# 4-Channel-Relay-Driver-Module-Circuit_20.net
KiCad netlist of a schematic drawn in Altium Designer
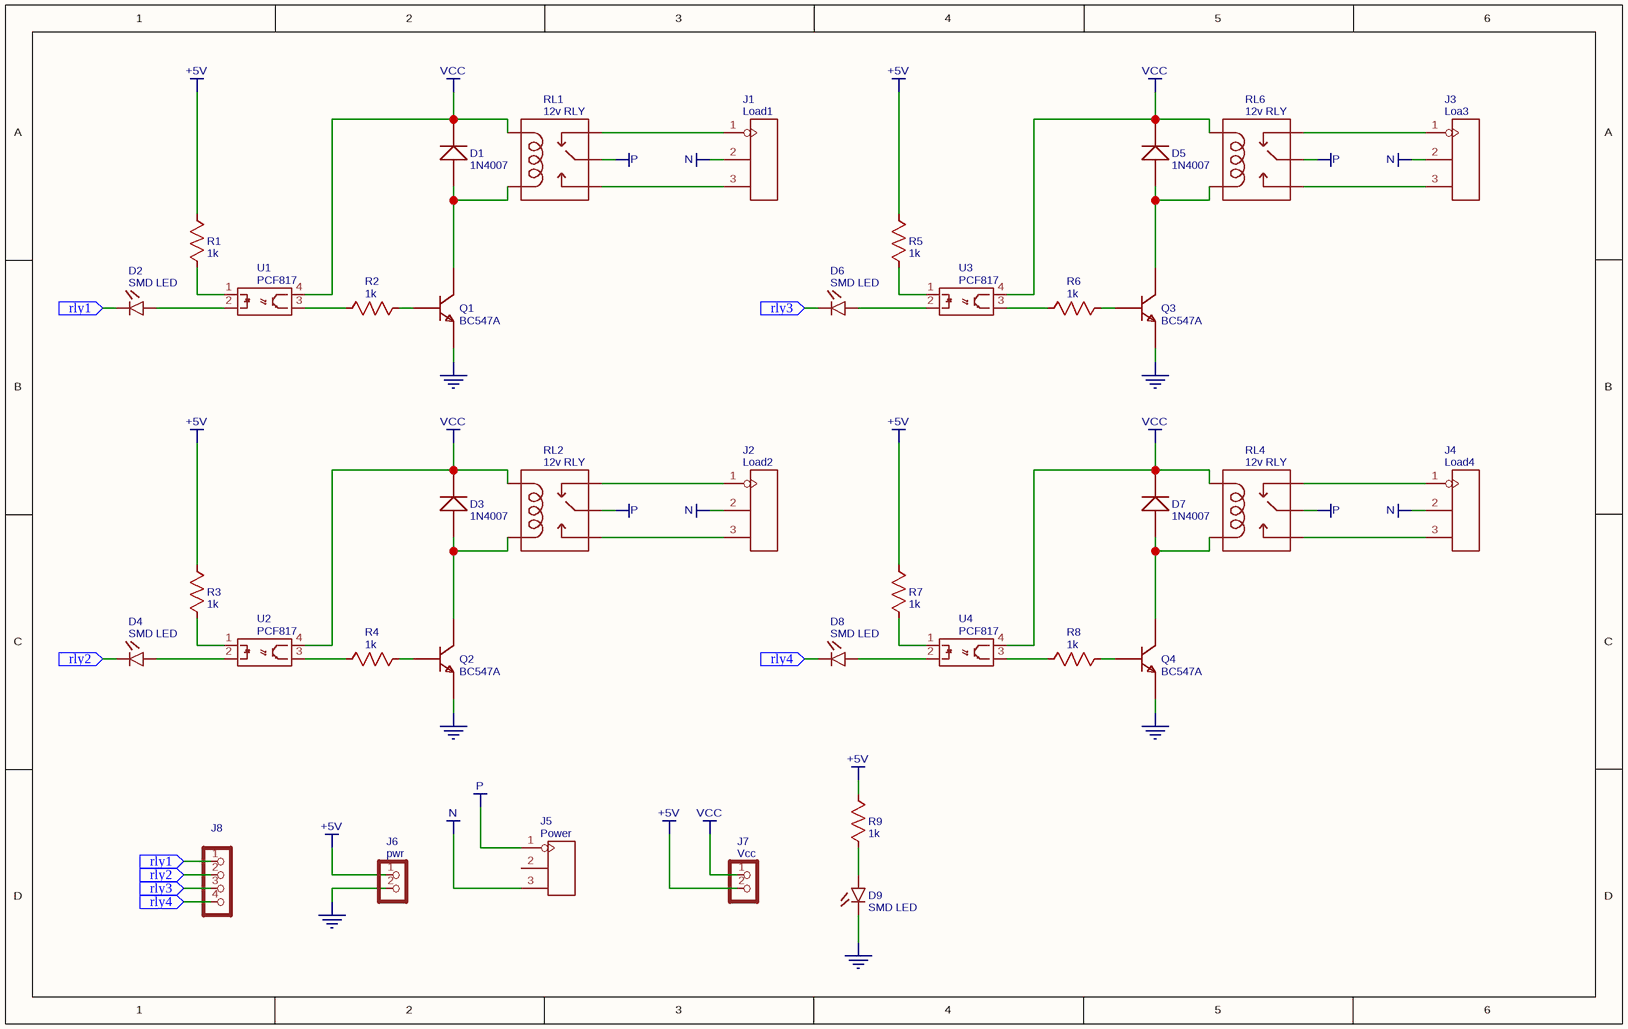
[diagram p0: 4-Channel-Relay-Driver-Module-Circuit_2024-05-24.schdoc]

(export (version "E")
  (design (tool "Eeschema 10.0.6"))
  (components
    (comp (ref "D1")
      (value "1N4007")
      (description "1.0 Ampere General Purpose Rectifier")
      (fields (field (name "MANUFACTURER PART") "?"))
      (libsource (lib "altium-import") (part "root_1_1N4007_"))
    )
    (comp (ref "D2")
      (value "SMD LED")
      (fields (field (name "MANUFACTURER PART") "?"))
      (libsource (lib "altium-import") (part "root_3_SMD LED_"))
    )
    (comp (ref "D3")
      (value "1N4007")
      (description "1.0 Ampere General Purpose Rectifier")
      (fields (field (name "MANUFACTURER PART") "?"))
      (libsource (lib "altium-import") (part "root_1_1N4007_"))
    )
    (comp (ref "D4")
      (value "SMD LED")
      (fields (field (name "MANUFACTURER PART") "?"))
      (libsource (lib "altium-import") (part "root_3_SMD LED_"))
    )
    (comp (ref "D5")
      (value "1N4007")
      (description "1.0 Ampere General Purpose Rectifier")
      (fields (field (name "MANUFACTURER PART") "?"))
      (libsource (lib "altium-import") (part "root_1_1N4007_"))
    )
    (comp (ref "D6")
      (value "SMD LED")
      (fields (field (name "MANUFACTURER PART") "?"))
      (libsource (lib "altium-import") (part "root_3_SMD LED_"))
    )
    (comp (ref "D7")
      (value "1N4007")
      (description "1.0 Ampere General Purpose Rectifier")
      (fields (field (name "MANUFACTURER PART") "?"))
      (libsource (lib "altium-import") (part "root_1_1N4007_"))
    )
    (comp (ref "D8")
      (value "SMD LED")
      (fields (field (name "MANUFACTURER PART") "?"))
      (libsource (lib "altium-import") (part "root_3_SMD LED_"))
    )
    (comp (ref "D9")
      (value "SMD LED")
      (fields (field (name "MANUFACTURER PART") "?"))
      (libsource (lib "altium-import") (part "root_0_SMD LED_"))
    )
    (comp (ref "J1")
      (value "Load1")
      (description "Screw Terminal")
      (fields (field (name "MANUFACTURER PART") "?"))
      (libsource (lib "altium-import") (part "root_0_Load1_"))
    )
    (comp (ref "J2")
      (value "Load2")
      (description "Screw Terminal")
      (fields (field (name "MANUFACTURER PART") "?"))
      (libsource (lib "altium-import") (part "root_0_Load2_"))
    )
    (comp (ref "J3")
      (value "Loa3")
      (description "Screw Terminal")
      (fields (field (name "MANUFACTURER PART") "?"))
      (libsource (lib "altium-import") (part "root_0_Loa3_"))
    )
    (comp (ref "J4")
      (value "Load4")
      (description "Screw Terminal")
      (fields (field (name "MANUFACTURER PART") "?"))
      (libsource (lib "altium-import") (part "root_0_Load4_"))
    )
    (comp (ref "J5")
      (value "Power")
      (description "Screw Terminal")
      (fields (field (name "MANUFACTURER PART") "?"))
      (libsource (lib "altium-import") (part "root_0_Power_"))
    )
    (comp (ref "J6")
      (value "pwr")
      (fields (field (name "MANUFACTURER PART") "?") (field (name "CONTRIBUTOR") "DangerousPrototype"))
      (libsource (lib "altium-import") (part "root_0_pwr_"))
    )
    (comp (ref "J7")
      (value "Vcc")
      (fields (field (name "MANUFACTURER PART") "?") (field (name "CONTRIBUTOR") "DangerousPrototype"))
      (libsource (lib "altium-import") (part "root_0_Vcc_"))
    )
    (comp (ref "J8")
      (value "+5v")
      (fields (field (name "MANUFACTURER PART") "?") (field (name "CONTRIBUTOR") "DangerousPrototype"))
      (libsource (lib "altium-import") (part "root_0_+5v_"))
    )
    (comp (ref "Q1")
      (value "BC547A")
      (description "Amplifier Transistor NPN Silicon")
      (fields (field (name "MANUFACTURER PART") "?"))
      (libsource (lib "altium-import") (part "root_0_BC547A_"))
    )
    (comp (ref "Q2")
      (value "BC547A")
      (description "Amplifier Transistor NPN Silicon")
      (fields (field (name "MANUFACTURER PART") "?"))
      (libsource (lib "altium-import") (part "root_0_BC547A_"))
    )
    (comp (ref "Q3")
      (value "BC547A")
      (description "Amplifier Transistor NPN Silicon")
      (fields (field (name "MANUFACTURER PART") "?"))
      (libsource (lib "altium-import") (part "root_0_BC547A_"))
    )
    (comp (ref "Q4")
      (value "BC547A")
      (description "Amplifier Transistor NPN Silicon")
      (fields (field (name "MANUFACTURER PART") "?"))
      (libsource (lib "altium-import") (part "root_0_BC547A_"))
    )
    (comp (ref "R1")
      (value "1k")
      (fields (field (name "MANUFACTURER PART") "?"))
      (libsource (lib "altium-import") (part "root_1_1k_"))
    )
    (comp (ref "R2")
      (value "1k")
      (fields (field (name "MANUFACTURER PART") "?"))
      (libsource (lib "altium-import") (part "root_2_1k_"))
    )
    (comp (ref "R3")
      (value "1k")
      (fields (field (name "MANUFACTURER PART") "?"))
      (libsource (lib "altium-import") (part "root_1_1k_"))
    )
    (comp (ref "R4")
      (value "1k")
      (fields (field (name "MANUFACTURER PART") "?"))
      (libsource (lib "altium-import") (part "root_2_1k_"))
    )
    (comp (ref "R5")
      (value "1k")
      (fields (field (name "MANUFACTURER PART") "?"))
      (libsource (lib "altium-import") (part "root_1_1k_"))
    )
    (comp (ref "R6")
      (value "1k")
      (fields (field (name "MANUFACTURER PART") "?"))
      (libsource (lib "altium-import") (part "root_2_1k_"))
    )
    (comp (ref "R7")
      (value "1k")
      (fields (field (name "MANUFACTURER PART") "?"))
      (libsource (lib "altium-import") (part "root_1_1k_"))
    )
    (comp (ref "R8")
      (value "1k")
      (fields (field (name "MANUFACTURER PART") "?"))
      (libsource (lib "altium-import") (part "root_2_1k_"))
    )
    (comp (ref "R9")
      (value "1k")
      (fields (field (name "MANUFACTURER PART") "?"))
      (libsource (lib "altium-import") (part "root_1_1k_"))
    )
    (comp (ref "RL1")
      (value "12v RLY")
      (fields (field (name "MANUFACTURER PART") "?"))
      (libsource (lib "altium-import") (part "root_0_12v RLY_"))
    )
    (comp (ref "RL2")
      (value "12v RLY")
      (fields (field (name "MANUFACTURER PART") "?"))
      (libsource (lib "altium-import") (part "root_0_12v RLY_"))
    )
    (comp (ref "RL4")
      (value "12v RLY")
      (fields (field (name "MANUFACTURER PART") "?"))
      (libsource (lib "altium-import") (part "root_0_12v RLY_"))
    )
    (comp (ref "RL6")
      (value "12v RLY")
      (fields (field (name "MANUFACTURER PART") "?"))
      (libsource (lib "altium-import") (part "root_0_12v RLY_"))
    )
    (comp (ref "U1")
      (value "PCF817")
      (fields (field (name "MANUFACTURER PART") "?") (field (name "CONTRIBUTOR") "KiCad"))
      (libsource (lib "altium-import") (part "root_0_PCF817_"))
    )
    (comp (ref "U2")
      (value "PCF817")
      (fields (field (name "MANUFACTURER PART") "?") (field (name "CONTRIBUTOR") "KiCad"))
      (libsource (lib "altium-import") (part "root_0_PCF817_"))
    )
    (comp (ref "U3")
      (value "PCF817")
      (fields (field (name "MANUFACTURER PART") "?") (field (name "CONTRIBUTOR") "KiCad"))
      (libsource (lib "altium-import") (part "root_0_PCF817_"))
    )
    (comp (ref "U4")
      (value "PCF817")
      (fields (field (name "MANUFACTURER PART") "?") (field (name "CONTRIBUTOR") "KiCad"))
      (libsource (lib "altium-import") (part "root_0_PCF817_"))
    )
  )
  (nets
    (net (code "1") (name "+5V") (class "Default")
      (node (ref "J6") (pin "1") (pinfunction "1_1") (pintype "passive"))
      (node (ref "J7") (pin "2") (pinfunction "2_2") (pintype "passive"))
      (node (ref "R1") (pin "2") (pinfunction "2_2") (pintype "passive"))
      (node (ref "R3") (pin "2") (pinfunction "2_2") (pintype "passive"))
      (node (ref "R5") (pin "2") (pinfunction "2_2") (pintype "passive"))
      (node (ref "R7") (pin "2") (pinfunction "2_2") (pintype "passive"))
      (node (ref "R9") (pin "2") (pinfunction "2_2") (pintype "passive"))
    )
    (net (code "2") (name "/rly1") (class "Default")
      (node (ref "D2") (pin "3") (pinfunction "CATHODE_3") (pintype "passive"))
      (node (ref "J8") (pin "1") (pinfunction "1_1") (pintype "passive"))
    )
    (net (code "3") (name "/rly2") (class "Default")
      (node (ref "D4") (pin "3") (pinfunction "CATHODE_3") (pintype "passive"))
      (node (ref "J8") (pin "2") (pinfunction "2_2") (pintype "passive"))
    )
    (net (code "4") (name "/rly3") (class "Default")
      (node (ref "D6") (pin "3") (pinfunction "CATHODE_3") (pintype "passive"))
      (node (ref "J8") (pin "3") (pinfunction "3_3") (pintype "passive"))
    )
    (net (code "5") (name "/rly4") (class "Default")
      (node (ref "D8") (pin "3") (pinfunction "CATHODE_3") (pintype "passive"))
      (node (ref "J8") (pin "4") (pinfunction "4_4") (pintype "passive"))
    )
    (net (code "6") (name "GND") (class "Default")
      (node (ref "D9") (pin "3") (pinfunction "CATHODE_3") (pintype "passive"))
      (node (ref "J6") (pin "2") (pinfunction "2_2") (pintype "passive"))
      (node (ref "Q1") (pin "3") (pinfunction "E_3") (pintype "passive"))
      (node (ref "Q2") (pin "3") (pinfunction "E_3") (pintype "passive"))
      (node (ref "Q3") (pin "3") (pinfunction "E_3") (pintype "passive"))
      (node (ref "Q4") (pin "3") (pinfunction "E_3") (pintype "passive"))
    )
    (net (code "7") (name "N") (class "Default")
      (node (ref "J1") (pin "2") (pinfunction "P$2_2") (pintype "passive"))
      (node (ref "J2") (pin "2") (pinfunction "P$2_2") (pintype "passive"))
      (node (ref "J3") (pin "2") (pinfunction "P$2_2") (pintype "passive"))
      (node (ref "J4") (pin "2") (pinfunction "P$2_2") (pintype "passive"))
      (node (ref "J5") (pin "3") (pinfunction "P$3_3") (pintype "passive"))
    )
    (net (code "8") (name "Net-(D1-A)") (class "Default")
      (node (ref "D1") (pin "1") (pinfunction "A_1") (pintype "passive"))
      (node (ref "Q1") (pin "1") (pinfunction "C_1") (pintype "passive"))
      (node (ref "RL1") (pin "5") (pinfunction "COIL1_5") (pintype "passive"))
    )
    (net (code "9") (name "Net-(D2-ANODE)") (class "Default")
      (node (ref "D2") (pin "1") (pinfunction "ANODE_1") (pintype "passive"))
      (node (ref "U1") (pin "2") (pinfunction "2_2") (pintype "passive"))
    )
    (net (code "10") (name "Net-(D3-A)") (class "Default")
      (node (ref "D3") (pin "1") (pinfunction "A_1") (pintype "passive"))
      (node (ref "Q2") (pin "1") (pinfunction "C_1") (pintype "passive"))
      (node (ref "RL2") (pin "5") (pinfunction "COIL1_5") (pintype "passive"))
    )
    (net (code "11") (name "Net-(D4-ANODE)") (class "Default")
      (node (ref "D4") (pin "1") (pinfunction "ANODE_1") (pintype "passive"))
      (node (ref "U2") (pin "2") (pinfunction "2_2") (pintype "passive"))
    )
    (net (code "12") (name "Net-(D5-A)") (class "Default")
      (node (ref "D5") (pin "1") (pinfunction "A_1") (pintype "passive"))
      (node (ref "Q3") (pin "1") (pinfunction "C_1") (pintype "passive"))
      (node (ref "RL6") (pin "5") (pinfunction "COIL1_5") (pintype "passive"))
    )
    (net (code "13") (name "Net-(D6-ANODE)") (class "Default")
      (node (ref "D6") (pin "1") (pinfunction "ANODE_1") (pintype "passive"))
      (node (ref "U3") (pin "2") (pinfunction "2_2") (pintype "passive"))
    )
    (net (code "14") (name "Net-(D7-A)") (class "Default")
      (node (ref "D7") (pin "1") (pinfunction "A_1") (pintype "passive"))
      (node (ref "Q4") (pin "1") (pinfunction "C_1") (pintype "passive"))
      (node (ref "RL4") (pin "5") (pinfunction "COIL1_5") (pintype "passive"))
    )
    (net (code "15") (name "Net-(D8-ANODE)") (class "Default")
      (node (ref "D8") (pin "1") (pinfunction "ANODE_1") (pintype "passive"))
      (node (ref "U4") (pin "2") (pinfunction "2_2") (pintype "passive"))
    )
    (net (code "16") (name "Net-(D9-ANODE)") (class "Default")
      (node (ref "D9") (pin "1") (pinfunction "ANODE_1") (pintype "passive"))
      (node (ref "R9") (pin "1") (pinfunction "1_1") (pintype "passive"))
    )
    (net (code "17") (name "Net-(J1-P$1)") (class "Default")
      (node (ref "J1") (pin "1") (pinfunction "P$1_1") (pintype "passive"))
      (node (ref "RL1") (pin "4") (pinfunction "NC_4") (pintype "passive"))
    )
    (net (code "18") (name "Net-(J1-P$3)") (class "Default")
      (node (ref "J1") (pin "3") (pinfunction "P$3_3") (pintype "passive"))
      (node (ref "RL1") (pin "3") (pinfunction "NO_3") (pintype "passive"))
    )
    (net (code "19") (name "Net-(J2-P$1)") (class "Default")
      (node (ref "J2") (pin "1") (pinfunction "P$1_1") (pintype "passive"))
      (node (ref "RL2") (pin "4") (pinfunction "NC_4") (pintype "passive"))
    )
    (net (code "20") (name "Net-(J2-P$3)") (class "Default")
      (node (ref "J2") (pin "3") (pinfunction "P$3_3") (pintype "passive"))
      (node (ref "RL2") (pin "3") (pinfunction "NO_3") (pintype "passive"))
    )
    (net (code "21") (name "Net-(J3-P$1)") (class "Default")
      (node (ref "J3") (pin "1") (pinfunction "P$1_1") (pintype "passive"))
      (node (ref "RL6") (pin "4") (pinfunction "NC_4") (pintype "passive"))
    )
    (net (code "22") (name "Net-(J3-P$3)") (class "Default")
      (node (ref "J3") (pin "3") (pinfunction "P$3_3") (pintype "passive"))
      (node (ref "RL6") (pin "3") (pinfunction "NO_3") (pintype "passive"))
    )
    (net (code "23") (name "Net-(J4-P$1)") (class "Default")
      (node (ref "J4") (pin "1") (pinfunction "P$1_1") (pintype "passive"))
      (node (ref "RL4") (pin "4") (pinfunction "NC_4") (pintype "passive"))
    )
    (net (code "24") (name "Net-(J4-P$3)") (class "Default")
      (node (ref "J4") (pin "3") (pinfunction "P$3_3") (pintype "passive"))
      (node (ref "RL4") (pin "3") (pinfunction "NO_3") (pintype "passive"))
    )
    (net (code "25") (name "Net-(Q1-B)") (class "Default")
      (node (ref "Q1") (pin "2") (pinfunction "B_2") (pintype "passive"))
      (node (ref "R2") (pin "1") (pinfunction "1_1") (pintype "passive"))
    )
    (net (code "26") (name "Net-(Q2-B)") (class "Default")
      (node (ref "Q2") (pin "2") (pinfunction "B_2") (pintype "passive"))
      (node (ref "R4") (pin "1") (pinfunction "1_1") (pintype "passive"))
    )
    (net (code "27") (name "Net-(Q3-B)") (class "Default")
      (node (ref "Q3") (pin "2") (pinfunction "B_2") (pintype "passive"))
      (node (ref "R6") (pin "1") (pinfunction "1_1") (pintype "passive"))
    )
    (net (code "28") (name "Net-(Q4-B)") (class "Default")
      (node (ref "Q4") (pin "2") (pinfunction "B_2") (pintype "passive"))
      (node (ref "R8") (pin "1") (pinfunction "1_1") (pintype "passive"))
    )
    (net (code "29") (name "Net-(R1-Pad1)") (class "Default")
      (node (ref "R1") (pin "1") (pinfunction "1_1") (pintype "passive"))
      (node (ref "U1") (pin "1") (pinfunction "1_1") (pintype "passive"))
    )
    (net (code "30") (name "Net-(R2-Pad2)") (class "Default")
      (node (ref "R2") (pin "2") (pinfunction "2_2") (pintype "passive"))
      (node (ref "U1") (pin "3") (pinfunction "3_3") (pintype "passive"))
    )
    (net (code "31") (name "Net-(R3-Pad1)") (class "Default")
      (node (ref "R3") (pin "1") (pinfunction "1_1") (pintype "passive"))
      (node (ref "U2") (pin "1") (pinfunction "1_1") (pintype "passive"))
    )
    (net (code "32") (name "Net-(R4-Pad2)") (class "Default")
      (node (ref "R4") (pin "2") (pinfunction "2_2") (pintype "passive"))
      (node (ref "U2") (pin "3") (pinfunction "3_3") (pintype "passive"))
    )
    (net (code "33") (name "Net-(R5-Pad1)") (class "Default")
      (node (ref "R5") (pin "1") (pinfunction "1_1") (pintype "passive"))
      (node (ref "U3") (pin "1") (pinfunction "1_1") (pintype "passive"))
    )
    (net (code "34") (name "Net-(R6-Pad2)") (class "Default")
      (node (ref "R6") (pin "2") (pinfunction "2_2") (pintype "passive"))
      (node (ref "U3") (pin "3") (pinfunction "3_3") (pintype "passive"))
    )
    (net (code "35") (name "Net-(R7-Pad1)") (class "Default")
      (node (ref "R7") (pin "1") (pinfunction "1_1") (pintype "passive"))
      (node (ref "U4") (pin "1") (pinfunction "1_1") (pintype "passive"))
    )
    (net (code "36") (name "Net-(R8-Pad2)") (class "Default")
      (node (ref "R8") (pin "2") (pinfunction "2_2") (pintype "passive"))
      (node (ref "U4") (pin "3") (pinfunction "3_3") (pintype "passive"))
    )
    (net (code "37") (name "P") (class "Default")
      (node (ref "J5") (pin "1") (pinfunction "P$1_1") (pintype "passive"))
      (node (ref "RL1") (pin "1") (pinfunction "MAIN_1") (pintype "passive"))
      (node (ref "RL2") (pin "1") (pinfunction "MAIN_1") (pintype "passive"))
      (node (ref "RL4") (pin "1") (pinfunction "MAIN_1") (pintype "passive"))
      (node (ref "RL6") (pin "1") (pinfunction "MAIN_1") (pintype "passive"))
    )
    (net (code "38") (name "VCC") (class "Default")
      (node (ref "D1") (pin "2") (pinfunction "K_2") (pintype "passive"))
      (node (ref "D3") (pin "2") (pinfunction "K_2") (pintype "passive"))
      (node (ref "D5") (pin "2") (pinfunction "K_2") (pintype "passive"))
      (node (ref "D7") (pin "2") (pinfunction "K_2") (pintype "passive"))
      (node (ref "J7") (pin "1") (pinfunction "1_1") (pintype "passive"))
      (node (ref "RL1") (pin "2") (pinfunction "COIL2_2") (pintype "passive"))
      (node (ref "RL2") (pin "2") (pinfunction "COIL2_2") (pintype "passive"))
      (node (ref "RL4") (pin "2") (pinfunction "COIL2_2") (pintype "passive"))
      (node (ref "RL6") (pin "2") (pinfunction "COIL2_2") (pintype "passive"))
      (node (ref "U1") (pin "4") (pinfunction "4_4") (pintype "passive"))
      (node (ref "U2") (pin "4") (pinfunction "4_4") (pintype "passive"))
      (node (ref "U3") (pin "4") (pinfunction "4_4") (pintype "passive"))
      (node (ref "U4") (pin "4") (pinfunction "4_4") (pintype "passive"))
    )
    (net (code "39") (name "unconnected-(J5-P$2-Pad2)") (class "Default")
      (node (ref "J5") (pin "2") (pinfunction "P$2_2") (pintype "passive"))
    )
  )
)
